# OpAmps.net
KiCad netlist of a schematic drawn in Altium Designer
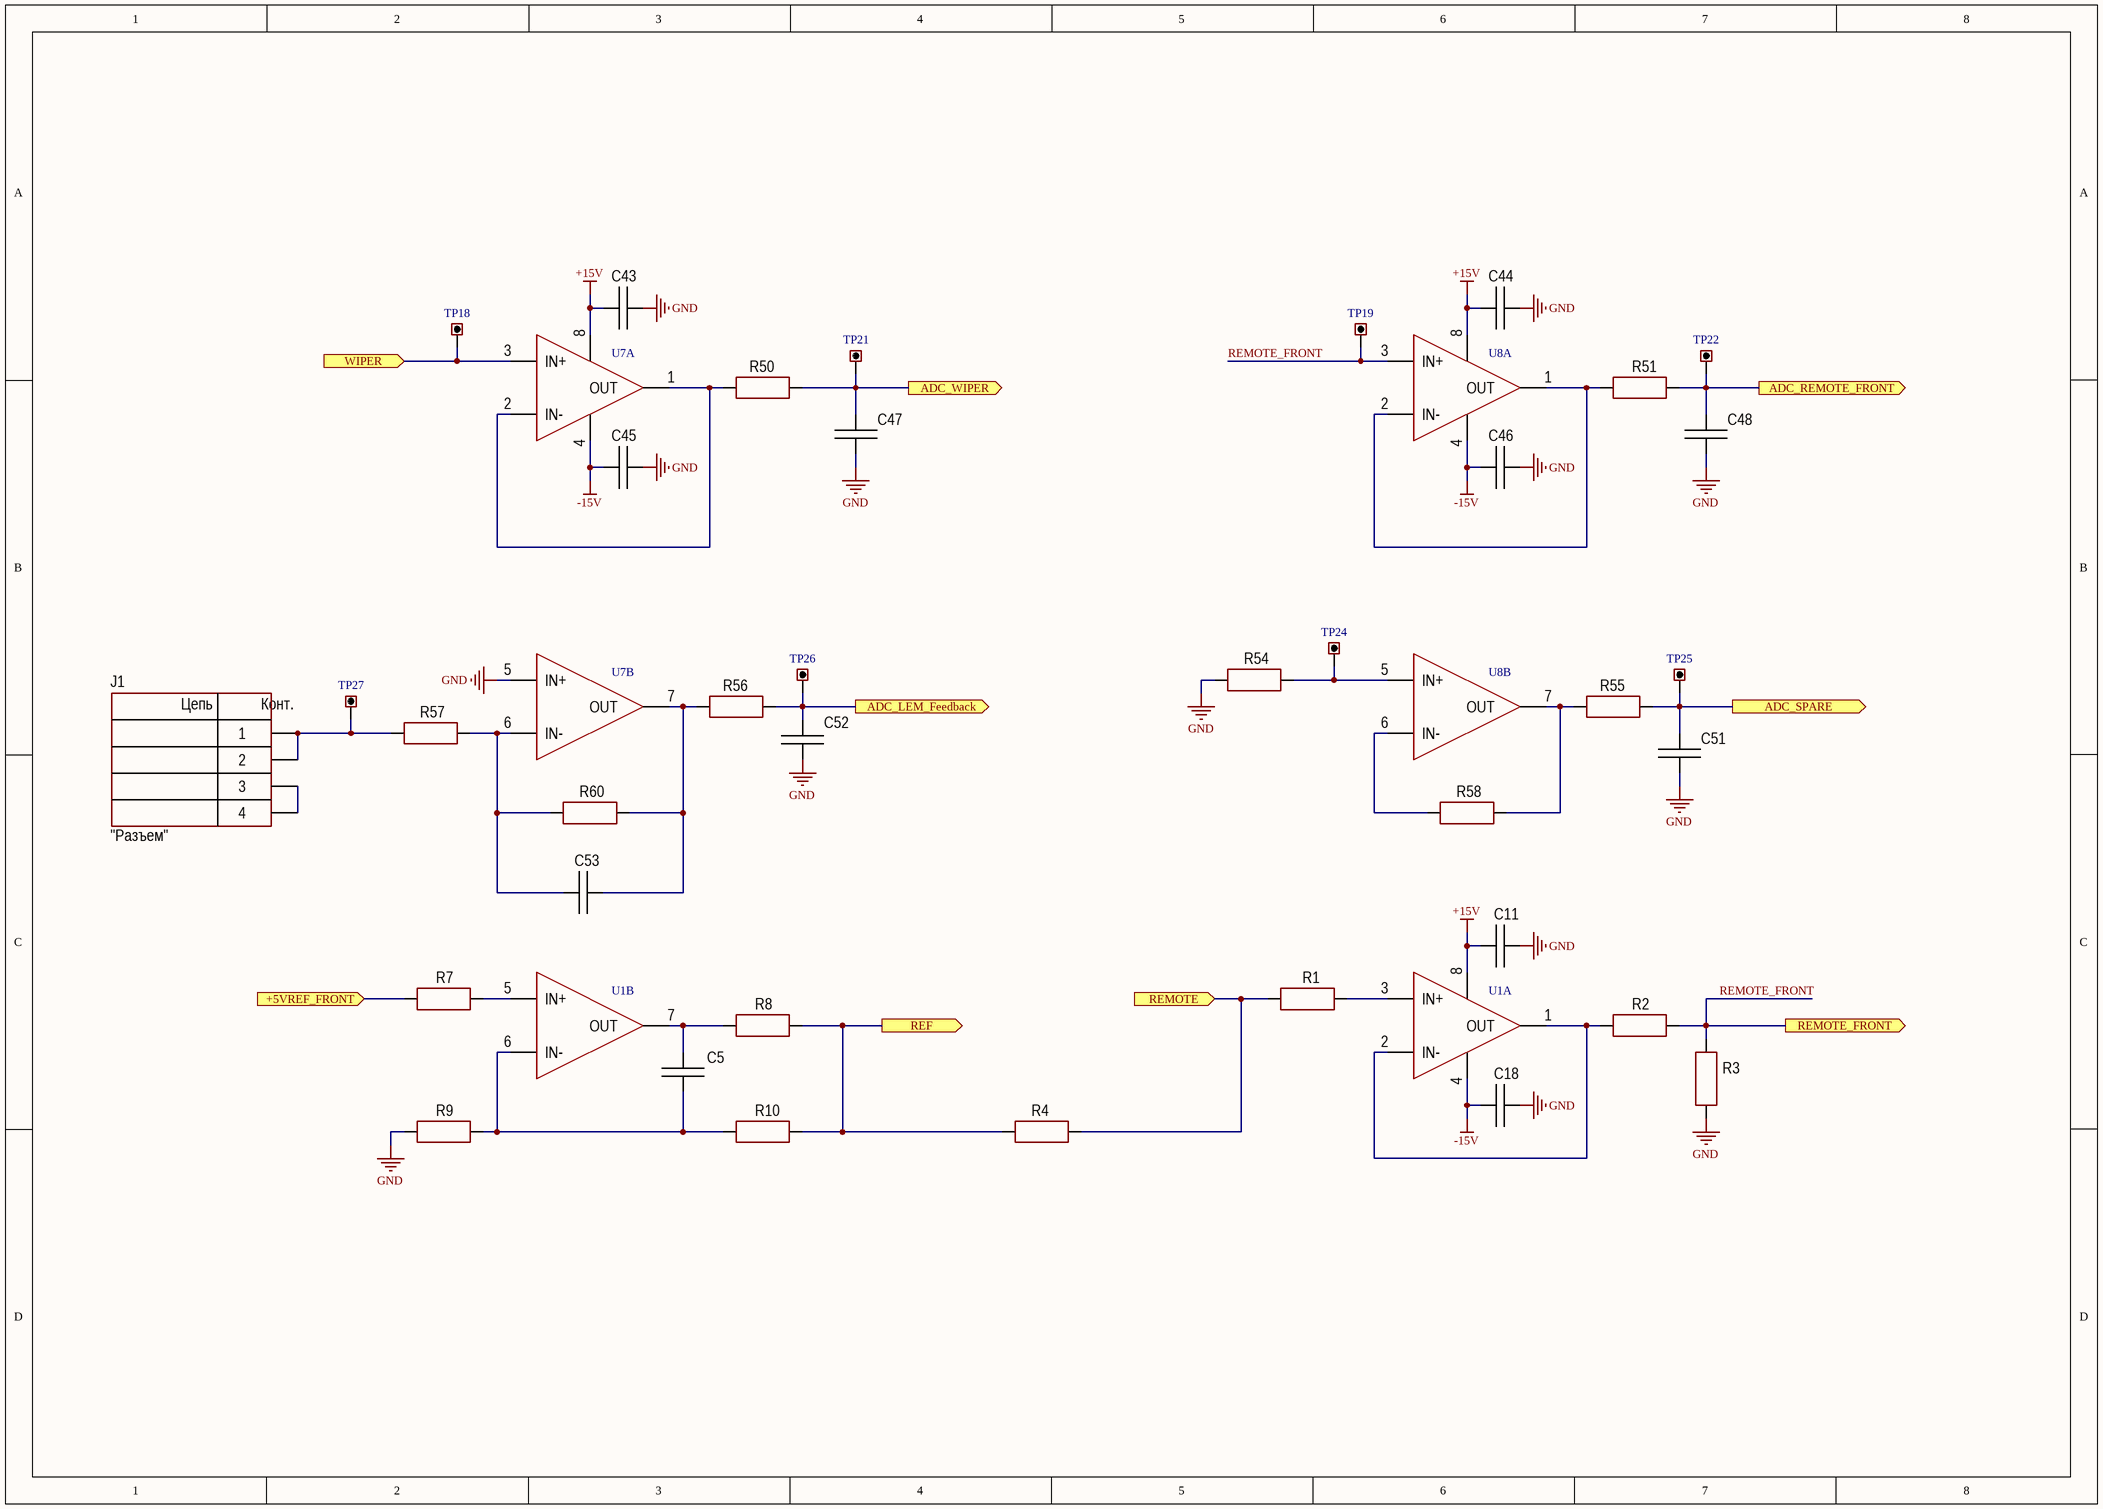
[diagram p0: OpAmps.SchDoc]

(export (version "E")
  (design (tool "Eeschema 10.0.6"))
  (components
    (comp (ref "C5")
      (value "~")
      (footprint "StandardCase:CAP: 1206")
      (fields
        (field (name "MANUFACTURER") "Yageo")
        (field (name "PARTNUMBER") "CC1206KRX7R9BB104")
        (field (name "VALUEMANUFACTURERPARTNUMBER") "Ceramic capacitor, 0.1μF, 1206")
      )
      (libsource (lib "Capacitor") (part "Ceramic_1206"))
    )
    (comp (ref "C11")
      (value "~")
      (footprint "StandardCase:CAP: 1206")
      (fields
        (field (name "MANUFACTURER") "Yageo")
        (field (name "PARTNUMBER") "CC1206KRX7R9BB104")
        (field (name "VALUEMANUFACTURERPARTNUMBER") "Ceramic capacitor, 0.1μF, 1206")
      )
      (libsource (lib "Capacitor") (part "Ceramic_1206"))
    )
    (comp (ref "C18")
      (value "~")
      (footprint "StandardCase:CAP: 1206")
      (fields
        (field (name "MANUFACTURER") "Yageo")
        (field (name "PARTNUMBER") "CC1206KRX7R9BB104")
        (field (name "VALUEMANUFACTURERPARTNUMBER") "Ceramic capacitor, 0.1μF, 1206")
      )
      (libsource (lib "Capacitor") (part "Ceramic_1206"))
    )
    (comp (ref "C43")
      (value "~")
      (footprint "StandardCase:CAP: 1206")
      (fields
        (field (name "MANUFACTURER") "Yageo")
        (field (name "PARTNUMBER") "CC1206KRX7R9BB104")
        (field (name "VALUEMANUFACTURERPARTNUMBER") "Ceramic capacitor, 0.1μF, 1206")
      )
      (libsource (lib "Capacitor") (part "Ceramic_1206"))
    )
    (comp (ref "C44")
      (value "~")
      (footprint "StandardCase:CAP: 1206")
      (fields
        (field (name "MANUFACTURER") "Yageo")
        (field (name "PARTNUMBER") "CC1206KRX7R9BB104")
        (field (name "VALUEMANUFACTURERPARTNUMBER") "Ceramic capacitor, 0.1μF, 1206")
      )
      (libsource (lib "Capacitor") (part "Ceramic_1206"))
    )
    (comp (ref "C45")
      (value "~")
      (footprint "StandardCase:CAP: 1206")
      (fields
        (field (name "MANUFACTURER") "Yageo")
        (field (name "PARTNUMBER") "CC1206KRX7R9BB104")
        (field (name "VALUEMANUFACTURERPARTNUMBER") "Ceramic capacitor, 0.1μF, 1206")
      )
      (libsource (lib "Capacitor") (part "Ceramic_1206"))
    )
    (comp (ref "C46")
      (value "~")
      (footprint "StandardCase:CAP: 1206")
      (fields
        (field (name "MANUFACTURER") "Yageo")
        (field (name "PARTNUMBER") "CC1206KRX7R9BB104")
        (field (name "VALUEMANUFACTURERPARTNUMBER") "Ceramic capacitor, 0.1μF, 1206")
      )
      (libsource (lib "Capacitor") (part "Ceramic_1206"))
    )
    (comp (ref "C47")
      (value "~")
      (footprint "StandardCase:CAP: 1206")
      (fields
        (field (name "MANUFACTURER") "Yageo")
        (field (name "PARTNUMBER") "CC1206KRX7R9BB104")
        (field (name "VALUEMANUFACTURERPARTNUMBER") "Ceramic capacitor, 33pF, 1206")
      )
      (libsource (lib "Capacitor") (part "Ceramic_1206"))
    )
    (comp (ref "C48")
      (value "~")
      (footprint "StandardCase:CAP: 1206")
      (fields
        (field (name "MANUFACTURER") "Yageo")
        (field (name "PARTNUMBER") "CC1206KRX7R9BB104")
        (field (name "VALUEMANUFACTURERPARTNUMBER") "Ceramic capacitor, 33pF, 1206")
      )
      (libsource (lib "Capacitor") (part "Ceramic_1206"))
    )
    (comp (ref "C51")
      (value "~")
      (footprint "StandardCase:CAP: 1206")
      (fields
        (field (name "MANUFACTURER") "Yageo")
        (field (name "PARTNUMBER") "CC1206KRX7R9BB104")
        (field (name "VALUEMANUFACTURERPARTNUMBER") "Ceramic capacitor, 33pF, 1206")
      )
      (libsource (lib "Capacitor") (part "Ceramic_1206"))
    )
    (comp (ref "C52")
      (value "~")
      (footprint "StandardCase:CAP: 1206")
      (fields
        (field (name "MANUFACTURER") "Yageo")
        (field (name "PARTNUMBER") "CC1206KRX7R9BB104")
        (field (name "VALUEMANUFACTURERPARTNUMBER") "Ceramic capacitor, 33pF, 1206")
      )
      (libsource (lib "Capacitor") (part "Ceramic_1206"))
    )
    (comp (ref "C53")
      (value "~")
      (footprint "StandardCase:CAP: 1206")
      (fields
        (field (name "MANUFACTURER") "Yageo")
        (field (name "PARTNUMBER") "CC1206KRX7R9BB104")
        (field (name "VALUEMANUFACTURERPARTNUMBER") "Ceramic capacitor, 0.1μF, 1206")
      )
      (libsource (lib "Capacitor") (part "Ceramic_1206"))
    )
    (comp (ref "J1")
      (value "~")
      (footprint "FP_lib_PCB:39-29-9043")
      (fields
        (field (name "MANUFACTURER") "MOLEX")
        (field (name "VALUEMANUFACTURERPARTNUMBER") "Connector, MOLEX, 39-29-9043, 4pin")
        (field (name "PARTNUMBER") "39-29-9043")
        (field (name "COMMENTTEXT") "\"Разъем\"")
      )
      (libsource (lib "Connector") (part "PBD-4"))
    )
    (comp (ref "R1")
      (value "~")
      (footprint "StandardCase:RES: 1206")
      (fields
        (field (name "MANUFACTURER") "Yageo")
        (field (name "PARTNUMBER") "RC1206JR-07100RL")
        (field (name "VALUEMANUFACTURERPARTNUMBER") "Resistor, 10K, 1206")
      )
      (libsource (lib "Resistor") (part "Resistor_1206"))
    )
    (comp (ref "R2")
      (value "~")
      (footprint "StandardCase:RES: 1206")
      (fields
        (field (name "MANUFACTURER") "Yageo")
        (field (name "PARTNUMBER") "RC1206JR-07100RL")
        (field (name "VALUEMANUFACTURERPARTNUMBER") "Resistor, 2K, 1206")
      )
      (libsource (lib "Resistor") (part "Resistor_1206"))
    )
    (comp (ref "R3")
      (value "~")
      (footprint "StandardCase:RES: 1206")
      (fields
        (field (name "MANUFACTURER") "Yageo")
        (field (name "PARTNUMBER") "RC1206JR-07100RL")
        (field (name "VALUEMANUFACTURERPARTNUMBER") "Resistor, 2K, 1206")
      )
      (libsource (lib "") (part "Resistor_1206_1"))
    )
    (comp (ref "R4")
      (value "~")
      (footprint "StandardCase:RES: 1206")
      (fields
        (field (name "MANUFACTURER") "Yageo")
        (field (name "PARTNUMBER") "RC1206JR-07100RL")
        (field (name "VALUEMANUFACTURERPARTNUMBER") "Resistor, 100K, 1206")
      )
      (libsource (lib "Resistor") (part "Resistor_1206"))
    )
    (comp (ref "R7")
      (value "~")
      (footprint "StandardCase:RES: 1206")
      (fields
        (field (name "MANUFACTURER") "Yageo")
        (field (name "PARTNUMBER") "RC1206JR-07100RL")
        (field (name "VALUEMANUFACTURERPARTNUMBER") "Resistor, 10K, 1206")
      )
      (libsource (lib "Resistor") (part "Resistor_1206"))
    )
    (comp (ref "R8")
      (value "~")
      (footprint "StandardCase:RES: 1206")
      (fields
        (field (name "MANUFACTURER") "Yageo")
        (field (name "PARTNUMBER") "RC1206JR-07100RL")
        (field (name "VALUEMANUFACTURERPARTNUMBER") "Resistor, 10R, 1206")
      )
      (libsource (lib "Resistor") (part "Resistor_1206"))
    )
    (comp (ref "R9")
      (value "~")
      (footprint "StandardCase:RES: 1206")
      (fields
        (field (name "MANUFACTURER") "Yageo")
        (field (name "PARTNUMBER") "RC1206JR-07100RL")
        (field (name "VALUEMANUFACTURERPARTNUMBER") "Resistor, 10K, 1206")
      )
      (libsource (lib "Resistor") (part "Resistor_1206"))
    )
    (comp (ref "R10")
      (value "~")
      (footprint "StandardCase:RES: 1206")
      (fields
        (field (name "MANUFACTURER") "Yageo")
        (field (name "PARTNUMBER") "RC1206JR-07100RL")
        (field (name "VALUEMANUFACTURERPARTNUMBER") "Resistor, 10K, 1206")
      )
      (libsource (lib "Resistor") (part "Resistor_1206"))
    )
    (comp (ref "R50")
      (value "~")
      (footprint "StandardCase:RES: 1206")
      (fields
        (field (name "MANUFACTURER") "Yageo")
        (field (name "PARTNUMBER") "RC1206JR-07100RL")
        (field (name "VALUEMANUFACTURERPARTNUMBER") "Resistor, 1K, 1206")
      )
      (libsource (lib "Resistor") (part "Resistor_1206"))
    )
    (comp (ref "R51")
      (value "~")
      (footprint "StandardCase:RES: 1206")
      (fields
        (field (name "MANUFACTURER") "Yageo")
        (field (name "PARTNUMBER") "RC1206JR-07100RL")
        (field (name "VALUEMANUFACTURERPARTNUMBER") "Resistor, 1K, 1206")
      )
      (libsource (lib "Resistor") (part "Resistor_1206"))
    )
    (comp (ref "R54")
      (value "~")
      (footprint "StandardCase:RES: 1206")
      (fields
        (field (name "MANUFACTURER") "Yageo")
        (field (name "PARTNUMBER") "RC1206JR-07100RL")
        (field (name "VALUEMANUFACTURERPARTNUMBER") "Resistor, 10K, 1206")
      )
      (libsource (lib "Resistor") (part "Resistor_1206"))
    )
    (comp (ref "R55")
      (value "~")
      (footprint "StandardCase:RES: 1206")
      (fields
        (field (name "MANUFACTURER") "Yageo")
        (field (name "PARTNUMBER") "RC1206JR-07100RL")
        (field (name "VALUEMANUFACTURERPARTNUMBER") "Resistor, 1K, 1206")
      )
      (libsource (lib "Resistor") (part "Resistor_1206"))
    )
    (comp (ref "R56")
      (value "~")
      (footprint "StandardCase:RES: 1206")
      (fields
        (field (name "MANUFACTURER") "Yageo")
        (field (name "PARTNUMBER") "RC1206JR-07100RL")
        (field (name "VALUEMANUFACTURERPARTNUMBER") "Resistor, 1K, 1206")
      )
      (libsource (lib "Resistor") (part "Resistor_1206"))
    )
    (comp (ref "R57")
      (value "~")
      (footprint "StandardCase:RES: 1206")
      (fields
        (field (name "MANUFACTURER") "Yageo")
        (field (name "PARTNUMBER") "RC1206JR-07100RL")
        (field (name "VALUEMANUFACTURERPARTNUMBER") "Resistor, 20K, 1206")
      )
      (libsource (lib "Resistor") (part "Resistor_1206"))
    )
    (comp (ref "R58")
      (value "~")
      (footprint "StandardCase:RES: 1206")
      (fields
        (field (name "MANUFACTURER") "Yageo")
        (field (name "PARTNUMBER") "RC1206JR-07100RL")
        (field (name "VALUEMANUFACTURERPARTNUMBER") "Resistor, 10K, 1206")
      )
      (libsource (lib "Resistor") (part "Resistor_1206"))
    )
    (comp (ref "R60")
      (value "~")
      (footprint "StandardCase:RES: 1206")
      (fields
        (field (name "MANUFACTURER") "Yageo")
        (field (name "PARTNUMBER") "RC1206JR-07100RL")
        (field (name "VALUEMANUFACTURERPARTNUMBER") "Resistor, 10K, 1206")
      )
      (libsource (lib "Resistor") (part "Resistor_1206"))
    )
    (comp (ref "TP18")
      (value "Test_Point")
      (footprint "FP_lib_PCB:Test_Point")
      (libsource (lib "FP_lib_SCH") (part "Test_Point"))
    )
    (comp (ref "TP19")
      (value "Test_Point")
      (footprint "FP_lib_PCB:Test_Point")
      (libsource (lib "FP_lib_SCH") (part "Test_Point"))
    )
    (comp (ref "TP21")
      (value "Test_Point")
      (footprint "FP_lib_PCB:Test_Point")
      (libsource (lib "FP_lib_SCH") (part "Test_Point"))
    )
    (comp (ref "TP22")
      (value "Test_Point")
      (footprint "FP_lib_PCB:Test_Point")
      (libsource (lib "FP_lib_SCH") (part "Test_Point"))
    )
    (comp (ref "TP24")
      (value "Test_Point")
      (footprint "FP_lib_PCB:Test_Point")
      (libsource (lib "FP_lib_SCH") (part "Test_Point"))
    )
    (comp (ref "TP25")
      (value "Test_Point")
      (footprint "FP_lib_PCB:Test_Point")
      (libsource (lib "FP_lib_SCH") (part "Test_Point"))
    )
    (comp (ref "TP26")
      (value "Test_Point")
      (footprint "FP_lib_PCB:Test_Point")
      (libsource (lib "FP_lib_SCH") (part "Test_Point"))
    )
    (comp (ref "TP27")
      (value "Test_Point")
      (footprint "FP_lib_PCB:Test_Point")
      (libsource (lib "FP_lib_SCH") (part "Test_Point"))
    )
    (comp (ref "U1")
      (value "~")
      (footprint "StandardCase:8-SOIC")
      (fields
        (field (name "VALUEMANUFACTURERPARTNUMBER") "TL082, SOIC-8")
        (field (name "PARTNUMBER") "TL082")
      )
      (libsource (lib "FP_lib_SCH") (part "TL082"))
    )
    (comp (ref "U7")
      (value "~")
      (footprint "StandardCase:8-SOIC")
      (fields
        (field (name "VALUEMANUFACTURERPARTNUMBER") "TL082, SOIC-8")
        (field (name "PARTNUMBER") "TL082")
      )
      (libsource (lib "FP_lib_SCH") (part "TL082"))
    )
    (comp (ref "U8")
      (value "~")
      (footprint "StandardCase:8-SOIC")
      (fields
        (field (name "VALUEMANUFACTURERPARTNUMBER") "TL082, SOIC-8")
        (field (name "PARTNUMBER") "TL082")
      )
      (libsource (lib "FP_lib_SCH") (part "TL082"))
    )
  )
  (nets
    (net (code "1") (name "+15V") (class "Default")
      (node (ref "C11") (pin "2") (pinfunction "2_2") (pintype "power_in"))
      (node (ref "C43") (pin "2") (pinfunction "2_2") (pintype "power_in"))
      (node (ref "C44") (pin "2") (pinfunction "2_2") (pintype "power_in"))
      (node (ref "U1") (pin "8") (pinfunction "V+_8") (pintype "passive"))
      (node (ref "U7") (pin "8") (pinfunction "V+_8") (pintype "passive"))
      (node (ref "U8") (pin "8") (pinfunction "V+_8") (pintype "passive"))
    )
    (net (code "2") (name "-15V") (class "Default")
      (node (ref "C18") (pin "1") (pinfunction "1_1") (pintype "power_in"))
      (node (ref "C45") (pin "2") (pinfunction "2_2") (pintype "power_in"))
      (node (ref "C46") (pin "2") (pinfunction "2_2") (pintype "power_in"))
      (node (ref "U1") (pin "4") (pinfunction "V-_4") (pintype "passive"))
      (node (ref "U7") (pin "4") (pinfunction "V-_4") (pintype "passive"))
      (node (ref "U8") (pin "4") (pinfunction "V-_4") (pintype "passive"))
    )
    (net (code "3") (name "/+5VREF_FRONT") (class "Default")
      (node (ref "R7") (pin "1") (pinfunction "1_1") (pintype "passive"))
    )
    (net (code "4") (name "/ADC_LEM_Feedback") (class "Default")
      (node (ref "C52") (pin "2") (pinfunction "2_2") (pintype "power_in"))
      (node (ref "R56") (pin "2") (pinfunction "2_2") (pintype "passive"))
      (node (ref "TP26") (pin "1") (pinfunction "1_1") (pintype "passive"))
    )
    (net (code "5") (name "/ADC_REMOTE_FRONT") (class "Default")
      (node (ref "C48") (pin "2") (pinfunction "2_2") (pintype "power_in"))
      (node (ref "R51") (pin "2") (pinfunction "2_2") (pintype "passive"))
      (node (ref "TP22") (pin "1") (pinfunction "1_1") (pintype "passive"))
    )
    (net (code "6") (name "/ADC_SPARE") (class "Default")
      (node (ref "C51") (pin "2") (pinfunction "2_2") (pintype "power_in"))
      (node (ref "R55") (pin "2") (pinfunction "2_2") (pintype "passive"))
      (node (ref "TP25") (pin "1") (pinfunction "1_1") (pintype "passive"))
    )
    (net (code "7") (name "/ADC_WIPER") (class "Default")
      (node (ref "C47") (pin "2") (pinfunction "2_2") (pintype "power_in"))
      (node (ref "R50") (pin "2") (pinfunction "2_2") (pintype "passive"))
      (node (ref "TP21") (pin "1") (pinfunction "1_1") (pintype "passive"))
    )
    (net (code "8") (name "/REF") (class "Default")
      (node (ref "R10") (pin "2") (pinfunction "2_2") (pintype "passive"))
      (node (ref "R4") (pin "1") (pinfunction "1_1") (pintype "passive"))
      (node (ref "R8") (pin "2") (pinfunction "2_2") (pintype "passive"))
    )
    (net (code "9") (name "/REMOTE") (class "Default")
      (node (ref "R1") (pin "1") (pinfunction "1_1") (pintype "passive"))
      (node (ref "R4") (pin "2") (pinfunction "2_2") (pintype "passive"))
    )
    (net (code "10") (name "/REMOTE_FRONT") (class "Default")
      (node (ref "R2") (pin "2") (pinfunction "2_2") (pintype "passive"))
      (node (ref "R3") (pin "2") (pinfunction "2_2") (pintype "passive"))
      (node (ref "TP19") (pin "1") (pinfunction "1_1") (pintype "passive"))
      (node (ref "U8") (pin "3") (pinfunction "IN+_3") (pintype "passive"))
    )
    (net (code "11") (name "/WIPER") (class "Default")
      (node (ref "TP18") (pin "1") (pinfunction "1_1") (pintype "passive"))
      (node (ref "U7") (pin "3") (pinfunction "IN+_3") (pintype "passive"))
    )
    (net (code "12") (name "GND") (class "Default")
      (node (ref "C11") (pin "1") (pinfunction "1_1") (pintype "power_in"))
      (node (ref "C18") (pin "2") (pinfunction "2_2") (pintype "power_in"))
      (node (ref "C43") (pin "1") (pinfunction "1_1") (pintype "power_in"))
      (node (ref "C44") (pin "1") (pinfunction "1_1") (pintype "power_in"))
      (node (ref "C45") (pin "1") (pinfunction "1_1") (pintype "power_in"))
      (node (ref "C46") (pin "1") (pinfunction "1_1") (pintype "power_in"))
      (node (ref "C47") (pin "1") (pinfunction "1_1") (pintype "power_in"))
      (node (ref "C48") (pin "1") (pinfunction "1_1") (pintype "power_in"))
      (node (ref "C51") (pin "1") (pinfunction "1_1") (pintype "power_in"))
      (node (ref "C52") (pin "1") (pinfunction "1_1") (pintype "power_in"))
      (node (ref "R3") (pin "1") (pinfunction "1_1") (pintype "passive"))
      (node (ref "R54") (pin "1") (pinfunction "1_1") (pintype "passive"))
      (node (ref "R9") (pin "1") (pinfunction "1_1") (pintype "passive"))
      (node (ref "U7") (pin "5") (pinfunction "IN+_5") (pintype "passive"))
    )
    (net (code "13") (name "Net-(J1-Pad1)") (class "Default")
      (node (ref "J1") (pin "1") (pinfunction "1_1") (pintype "passive"))
      (node (ref "J1") (pin "2") (pinfunction "2_2") (pintype "passive"))
      (node (ref "R57") (pin "1") (pinfunction "1_1") (pintype "passive"))
      (node (ref "TP27") (pin "1") (pinfunction "1_1") (pintype "passive"))
    )
    (net (code "14") (name "Net-(J1-Pad3)") (class "Default")
      (node (ref "J1") (pin "3") (pinfunction "3_3") (pintype "power_in"))
      (node (ref "J1") (pin "4") (pinfunction "4_4") (pintype "power_in"))
    )
    (net (code "15") (name "Net-(U1A-IN+)") (class "Default")
      (node (ref "R1") (pin "2") (pinfunction "2_2") (pintype "passive"))
      (node (ref "U1") (pin "3") (pinfunction "IN+_3") (pintype "passive"))
    )
    (net (code "16") (name "Net-(U1A-IN-)") (class "Default")
      (node (ref "R2") (pin "1") (pinfunction "1_1") (pintype "passive"))
      (node (ref "U1") (pin "1") (pinfunction "OUT_1") (pintype "passive"))
      (node (ref "U1") (pin "2") (pinfunction "IN-_2") (pintype "passive"))
    )
    (net (code "17") (name "Net-(U1B-IN+)") (class "Default")
      (node (ref "R7") (pin "2") (pinfunction "2_2") (pintype "passive"))
      (node (ref "U1") (pin "5") (pinfunction "IN+_5") (pintype "passive"))
    )
    (net (code "18") (name "Net-(U1B-IN-)") (class "Default")
      (node (ref "C5") (pin "1") (pinfunction "1_1") (pintype "power_in"))
      (node (ref "R10") (pin "1") (pinfunction "1_1") (pintype "passive"))
      (node (ref "R9") (pin "2") (pinfunction "2_2") (pintype "passive"))
      (node (ref "U1") (pin "6") (pinfunction "IN-_6") (pintype "passive"))
    )
    (net (code "19") (name "Net-(U1B-OUT)") (class "Default")
      (node (ref "C5") (pin "2") (pinfunction "2_2") (pintype "power_in"))
      (node (ref "R8") (pin "1") (pinfunction "1_1") (pintype "passive"))
      (node (ref "U1") (pin "7") (pinfunction "OUT_7") (pintype "passive"))
    )
    (net (code "20") (name "Net-(U7A-IN-)") (class "Default")
      (node (ref "R50") (pin "1") (pinfunction "1_1") (pintype "passive"))
      (node (ref "U7") (pin "1") (pinfunction "OUT_1") (pintype "passive"))
      (node (ref "U7") (pin "2") (pinfunction "IN-_2") (pintype "passive"))
    )
    (net (code "21") (name "Net-(U7B-IN-)") (class "Default")
      (node (ref "C53") (pin "2") (pinfunction "2_2") (pintype "power_in"))
      (node (ref "R57") (pin "2") (pinfunction "2_2") (pintype "passive"))
      (node (ref "R60") (pin "1") (pinfunction "1_1") (pintype "passive"))
      (node (ref "U7") (pin "6") (pinfunction "IN-_6") (pintype "passive"))
    )
    (net (code "22") (name "Net-(U7B-OUT)") (class "Default")
      (node (ref "C53") (pin "1") (pinfunction "1_1") (pintype "power_in"))
      (node (ref "R56") (pin "1") (pinfunction "1_1") (pintype "passive"))
      (node (ref "R60") (pin "2") (pinfunction "2_2") (pintype "passive"))
      (node (ref "U7") (pin "7") (pinfunction "OUT_7") (pintype "passive"))
    )
    (net (code "23") (name "Net-(U8A-IN-)") (class "Default")
      (node (ref "R51") (pin "1") (pinfunction "1_1") (pintype "passive"))
      (node (ref "U8") (pin "1") (pinfunction "OUT_1") (pintype "passive"))
      (node (ref "U8") (pin "2") (pinfunction "IN-_2") (pintype "passive"))
    )
    (net (code "24") (name "Net-(U8B-IN+)") (class "Default")
      (node (ref "R54") (pin "2") (pinfunction "2_2") (pintype "passive"))
      (node (ref "TP24") (pin "1") (pinfunction "1_1") (pintype "passive"))
      (node (ref "U8") (pin "5") (pinfunction "IN+_5") (pintype "passive"))
    )
    (net (code "25") (name "Net-(U8B-IN-)") (class "Default")
      (node (ref "R58") (pin "1") (pinfunction "1_1") (pintype "passive"))
      (node (ref "U8") (pin "6") (pinfunction "IN-_6") (pintype "passive"))
    )
    (net (code "26") (name "Net-(U8B-OUT)") (class "Default")
      (node (ref "R55") (pin "1") (pinfunction "1_1") (pintype "passive"))
      (node (ref "R58") (pin "2") (pinfunction "2_2") (pintype "passive"))
      (node (ref "U8") (pin "7") (pinfunction "OUT_7") (pintype "passive"))
    )
  )
)
